# Memory.net
KiCad netlist of a schematic drawn in Altium Designer
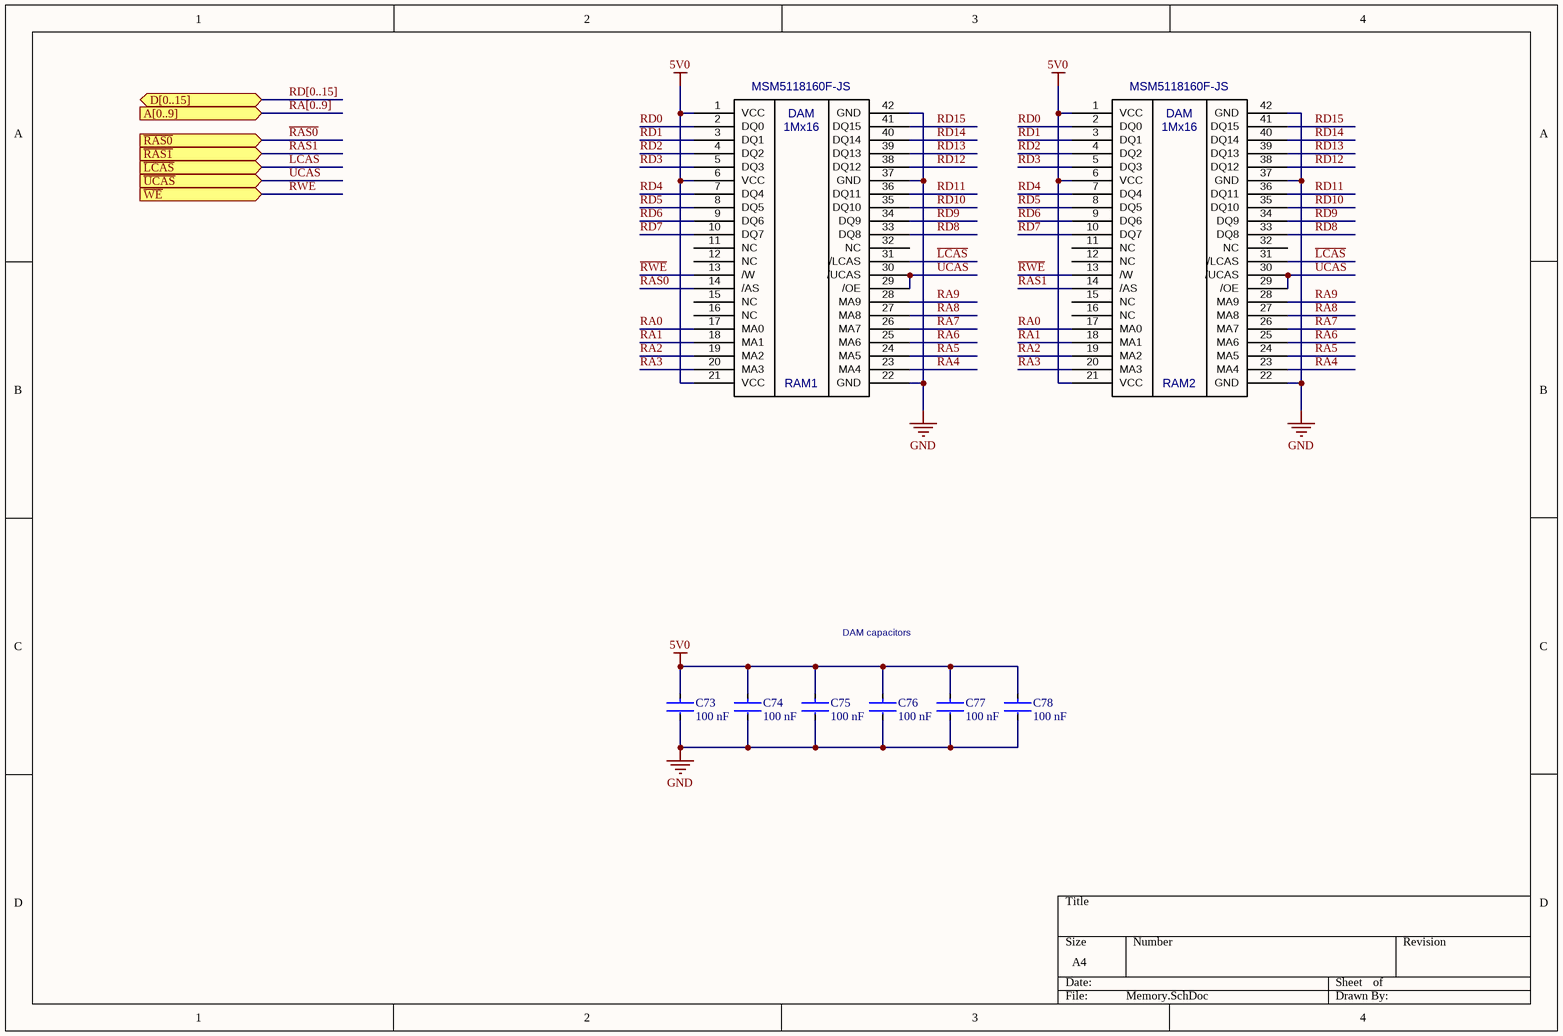
[diagram p0: Memory.SchDoc]

(export (version "E")
  (design (tool "Eeschema 10.0.6"))
  (components
    (comp (ref "C73")
      (value "CC0805-1.5pF")
      (footprint "CC0805")
      (description "CL21 Series 0805 1.5pF 50V ±0.25pF Tolerance C0G Multilayer Ceramic Chip Capacitor")
      (fields
        (field (name "MANUFACTURER PART NUMBER") "CL21C1R5CBANNNC")
        (field (name "CAPACITANCE") "100 nF")
        (field (name "MANUFACTURER") "Samsung")
      )
      (libsource (lib "zxevo") (part "CC0805"))
    )
    (comp (ref "C74")
      (value "CC0805-1.5pF")
      (footprint "CC0805")
      (description "CL21 Series 0805 1.5pF 50V ±0.25pF Tolerance C0G Multilayer Ceramic Chip Capacitor")
      (fields
        (field (name "MANUFACTURER PART NUMBER") "CL21C1R5CBANNNC")
        (field (name "CAPACITANCE") "100 nF")
        (field (name "MANUFACTURER") "Samsung")
      )
      (libsource (lib "zxevo") (part "CC0805"))
    )
    (comp (ref "C75")
      (value "CC0805-1.5pF")
      (footprint "CC0805")
      (description "CL21 Series 0805 1.5pF 50V ±0.25pF Tolerance C0G Multilayer Ceramic Chip Capacitor")
      (fields
        (field (name "MANUFACTURER PART NUMBER") "CL21C1R5CBANNNC")
        (field (name "CAPACITANCE") "100 nF")
        (field (name "MANUFACTURER") "Samsung")
      )
      (libsource (lib "zxevo") (part "CC0805"))
    )
    (comp (ref "C76")
      (value "CC0805-1.5pF")
      (footprint "CC0805")
      (description "CL21 Series 0805 1.5pF 50V ±0.25pF Tolerance C0G Multilayer Ceramic Chip Capacitor")
      (fields
        (field (name "MANUFACTURER PART NUMBER") "CL21C1R5CBANNNC")
        (field (name "CAPACITANCE") "100 nF")
        (field (name "MANUFACTURER") "Samsung")
      )
      (libsource (lib "zxevo") (part "CC0805"))
    )
    (comp (ref "C77")
      (value "CC0805-1.5pF")
      (footprint "CC0805")
      (description "CL21 Series 0805 1.5pF 50V ±0.25pF Tolerance C0G Multilayer Ceramic Chip Capacitor")
      (fields
        (field (name "MANUFACTURER PART NUMBER") "CL21C1R5CBANNNC")
        (field (name "CAPACITANCE") "100 nF")
        (field (name "MANUFACTURER") "Samsung")
      )
      (libsource (lib "zxevo") (part "CC0805"))
    )
    (comp (ref "C78")
      (value "CC0805-1.5pF")
      (footprint "CC0805")
      (description "CL21 Series 0805 1.5pF 50V ±0.25pF Tolerance C0G Multilayer Ceramic Chip Capacitor")
      (fields
        (field (name "MANUFACTURER PART NUMBER") "CL21C1R5CBANNNC")
        (field (name "CAPACITANCE") "100 nF")
        (field (name "MANUFACTURER") "Samsung")
      )
      (libsource (lib "zxevo") (part "CC0805"))
    )
    (comp (ref "RAM1")
      (value "MSM5118160F-JS")
      (footprint "SOJ42")
      (libsource (lib "zxevo") (part "MSM5118160F-JS"))
    )
    (comp (ref "RAM2")
      (value "MSM5118160F-JS")
      (footprint "SOJ42")
      (libsource (lib "zxevo") (part "MSM5118160F-JS"))
    )
  )
  (nets
    (net (code "1") (name "/RA0") (class "Default")
      (node (ref "RAM1") (pin "17") (pinfunction "MA0_17") (pintype "passive"))
      (node (ref "RAM2") (pin "17") (pinfunction "MA0_17") (pintype "passive"))
    )
    (net (code "2") (name "/RA1") (class "Default")
      (node (ref "RAM1") (pin "18") (pinfunction "MA1_18") (pintype "passive"))
      (node (ref "RAM2") (pin "18") (pinfunction "MA1_18") (pintype "passive"))
    )
    (net (code "3") (name "/RA2") (class "Default")
      (node (ref "RAM1") (pin "19") (pinfunction "MA2_19") (pintype "passive"))
      (node (ref "RAM2") (pin "19") (pinfunction "MA2_19") (pintype "passive"))
    )
    (net (code "4") (name "/RA3") (class "Default")
      (node (ref "RAM1") (pin "20") (pinfunction "MA3_20") (pintype "passive"))
      (node (ref "RAM2") (pin "20") (pinfunction "MA3_20") (pintype "passive"))
    )
    (net (code "5") (name "/RA4") (class "Default")
      (node (ref "RAM1") (pin "23") (pinfunction "MA4_23") (pintype "passive"))
      (node (ref "RAM2") (pin "23") (pinfunction "MA4_23") (pintype "passive"))
    )
    (net (code "6") (name "/RA5") (class "Default")
      (node (ref "RAM1") (pin "24") (pinfunction "MA5_24") (pintype "passive"))
      (node (ref "RAM2") (pin "24") (pinfunction "MA5_24") (pintype "passive"))
    )
    (net (code "7") (name "/RA6") (class "Default")
      (node (ref "RAM1") (pin "25") (pinfunction "MA6_25") (pintype "passive"))
      (node (ref "RAM2") (pin "25") (pinfunction "MA6_25") (pintype "passive"))
    )
    (net (code "8") (name "/RA7") (class "Default")
      (node (ref "RAM1") (pin "26") (pinfunction "MA7_26") (pintype "passive"))
      (node (ref "RAM2") (pin "26") (pinfunction "MA7_26") (pintype "passive"))
    )
    (net (code "9") (name "/RA8") (class "Default")
      (node (ref "RAM1") (pin "27") (pinfunction "MA8_27") (pintype "passive"))
      (node (ref "RAM2") (pin "27") (pinfunction "MA8_27") (pintype "passive"))
    )
    (net (code "10") (name "/RA9") (class "Default")
      (node (ref "RAM1") (pin "28") (pinfunction "MA9_28") (pintype "passive"))
      (node (ref "RAM2") (pin "28") (pinfunction "MA9_28") (pintype "passive"))
    )
    (net (code "12") (name "/RD0") (class "Default")
      (node (ref "RAM1") (pin "2") (pinfunction "DQ0_2") (pintype "passive"))
      (node (ref "RAM2") (pin "2") (pinfunction "DQ0_2") (pintype "passive"))
    )
    (net (code "13") (name "/RD1") (class "Default")
      (node (ref "RAM1") (pin "3") (pinfunction "DQ1_3") (pintype "passive"))
      (node (ref "RAM2") (pin "3") (pinfunction "DQ1_3") (pintype "passive"))
    )
    (net (code "14") (name "/RD2") (class "Default")
      (node (ref "RAM1") (pin "4") (pinfunction "DQ2_4") (pintype "passive"))
      (node (ref "RAM2") (pin "4") (pinfunction "DQ2_4") (pintype "passive"))
    )
    (net (code "15") (name "/RD3") (class "Default")
      (node (ref "RAM1") (pin "5") (pinfunction "DQ3_5") (pintype "passive"))
      (node (ref "RAM2") (pin "5") (pinfunction "DQ3_5") (pintype "passive"))
    )
    (net (code "16") (name "/RD4") (class "Default")
      (node (ref "RAM1") (pin "7") (pinfunction "DQ4_7") (pintype "passive"))
      (node (ref "RAM2") (pin "7") (pinfunction "DQ4_7") (pintype "passive"))
    )
    (net (code "17") (name "/RD5") (class "Default")
      (node (ref "RAM1") (pin "8") (pinfunction "DQ5_8") (pintype "passive"))
      (node (ref "RAM2") (pin "8") (pinfunction "DQ5_8") (pintype "passive"))
    )
    (net (code "18") (name "/RD6") (class "Default")
      (node (ref "RAM1") (pin "9") (pinfunction "DQ6_9") (pintype "passive"))
      (node (ref "RAM2") (pin "9") (pinfunction "DQ6_9") (pintype "passive"))
    )
    (net (code "19") (name "/RD7") (class "Default")
      (node (ref "RAM1") (pin "10") (pinfunction "DQ7_10") (pintype "passive"))
      (node (ref "RAM2") (pin "10") (pinfunction "DQ7_10") (pintype "passive"))
    )
    (net (code "20") (name "/RD8") (class "Default")
      (node (ref "RAM1") (pin "33") (pinfunction "DQ8_33") (pintype "passive"))
      (node (ref "RAM2") (pin "33") (pinfunction "DQ8_33") (pintype "passive"))
    )
    (net (code "21") (name "/RD9") (class "Default")
      (node (ref "RAM1") (pin "34") (pinfunction "DQ9_34") (pintype "passive"))
      (node (ref "RAM2") (pin "34") (pinfunction "DQ9_34") (pintype "passive"))
    )
    (net (code "22") (name "/RD10") (class "Default")
      (node (ref "RAM1") (pin "35") (pinfunction "DQ10_35") (pintype "passive"))
      (node (ref "RAM2") (pin "35") (pinfunction "DQ10_35") (pintype "passive"))
    )
    (net (code "23") (name "/RD11") (class "Default")
      (node (ref "RAM1") (pin "36") (pinfunction "DQ11_36") (pintype "passive"))
      (node (ref "RAM2") (pin "36") (pinfunction "DQ11_36") (pintype "passive"))
    )
    (net (code "24") (name "/RD12") (class "Default")
      (node (ref "RAM1") (pin "38") (pinfunction "DQ12_38") (pintype "passive"))
      (node (ref "RAM2") (pin "38") (pinfunction "DQ12_38") (pintype "passive"))
    )
    (net (code "25") (name "/RD13") (class "Default")
      (node (ref "RAM1") (pin "39") (pinfunction "DQ13_39") (pintype "passive"))
      (node (ref "RAM2") (pin "39") (pinfunction "DQ13_39") (pintype "passive"))
    )
    (net (code "26") (name "/RD14") (class "Default")
      (node (ref "RAM1") (pin "40") (pinfunction "DQ14_40") (pintype "passive"))
      (node (ref "RAM2") (pin "40") (pinfunction "DQ14_40") (pintype "passive"))
    )
    (net (code "27") (name "/RD15") (class "Default")
      (node (ref "RAM1") (pin "41") (pinfunction "DQ15_41") (pintype "passive"))
      (node (ref "RAM2") (pin "41") (pinfunction "DQ15_41") (pintype "passive"))
    )
    (net (code "29") (name "/~{LCAS}") (class "Default")
      (node (ref "RAM1") (pin "31") (pinfunction "/LCAS_31") (pintype "passive"))
      (node (ref "RAM2") (pin "31") (pinfunction "/LCAS_31") (pintype "passive"))
    )
    (net (code "30") (name "/~{RAS0}") (class "Default")
      (node (ref "RAM1") (pin "14") (pinfunction "/AS_14") (pintype "passive"))
    )
    (net (code "31") (name "/~{RAS1}") (class "Default")
      (node (ref "RAM2") (pin "14") (pinfunction "/AS_14") (pintype "passive"))
    )
    (net (code "32") (name "/~{RWE}") (class "Default")
      (node (ref "RAM1") (pin "13") (pinfunction "/W_13") (pintype "passive"))
      (node (ref "RAM2") (pin "13") (pinfunction "/W_13") (pintype "passive"))
    )
    (net (code "33") (name "/~{UCAS}") (class "Default")
      (node (ref "RAM1") (pin "29") (pinfunction "/OE_29") (pintype "passive"))
      (node (ref "RAM1") (pin "30") (pinfunction "/UCAS_30") (pintype "passive"))
      (node (ref "RAM2") (pin "29") (pinfunction "/OE_29") (pintype "passive"))
      (node (ref "RAM2") (pin "30") (pinfunction "/UCAS_30") (pintype "passive"))
    )
    (net (code "34") (name "5V0") (class "Default")
      (node (ref "C73") (pin "1") (pinfunction "1_1") (pintype "passive"))
      (node (ref "C74") (pin "1") (pinfunction "1_1") (pintype "passive"))
      (node (ref "C75") (pin "1") (pinfunction "1_1") (pintype "passive"))
      (node (ref "C76") (pin "1") (pinfunction "1_1") (pintype "passive"))
      (node (ref "C77") (pin "1") (pinfunction "1_1") (pintype "passive"))
      (node (ref "C78") (pin "1") (pinfunction "1_1") (pintype "passive"))
      (node (ref "RAM1") (pin "1") (pinfunction "VCC_1") (pintype "passive"))
      (node (ref "RAM1") (pin "21") (pinfunction "VCC_21") (pintype "passive"))
      (node (ref "RAM1") (pin "6") (pinfunction "VCC_6") (pintype "passive"))
      (node (ref "RAM2") (pin "1") (pinfunction "VCC_1") (pintype "passive"))
      (node (ref "RAM2") (pin "21") (pinfunction "VCC_21") (pintype "passive"))
      (node (ref "RAM2") (pin "6") (pinfunction "VCC_6") (pintype "passive"))
    )
    (net (code "35") (name "GND") (class "Default")
      (node (ref "C73") (pin "2") (pinfunction "2_2") (pintype "passive"))
      (node (ref "C74") (pin "2") (pinfunction "2_2") (pintype "passive"))
      (node (ref "C75") (pin "2") (pinfunction "2_2") (pintype "passive"))
      (node (ref "C76") (pin "2") (pinfunction "2_2") (pintype "passive"))
      (node (ref "C77") (pin "2") (pinfunction "2_2") (pintype "passive"))
      (node (ref "C78") (pin "2") (pinfunction "2_2") (pintype "passive"))
      (node (ref "RAM1") (pin "22") (pinfunction "GND_22") (pintype "passive"))
      (node (ref "RAM1") (pin "37") (pinfunction "GND_37") (pintype "passive"))
      (node (ref "RAM1") (pin "42") (pinfunction "GND_42") (pintype "passive"))
      (node (ref "RAM2") (pin "22") (pinfunction "GND_22") (pintype "passive"))
      (node (ref "RAM2") (pin "37") (pinfunction "GND_37") (pintype "passive"))
      (node (ref "RAM2") (pin "42") (pinfunction "GND_42") (pintype "passive"))
    )
    (net (code "36") (name "unconnected-(RAM1-NC-Pad11)") (class "Default")
      (node (ref "RAM1") (pin "11") (pinfunction "NC_11") (pintype "passive"))
    )
    (net (code "37") (name "unconnected-(RAM1-NC-Pad12)") (class "Default")
      (node (ref "RAM1") (pin "12") (pinfunction "NC_12") (pintype "passive"))
    )
    (net (code "38") (name "unconnected-(RAM1-NC-Pad15)") (class "Default")
      (node (ref "RAM1") (pin "15") (pinfunction "NC_15") (pintype "passive"))
    )
    (net (code "39") (name "unconnected-(RAM1-NC-Pad16)") (class "Default")
      (node (ref "RAM1") (pin "16") (pinfunction "NC_16") (pintype "passive"))
    )
    (net (code "40") (name "unconnected-(RAM1-NC-Pad32)") (class "Default")
      (node (ref "RAM1") (pin "32") (pinfunction "NC_32") (pintype "passive"))
    )
    (net (code "41") (name "unconnected-(RAM2-NC-Pad11)") (class "Default")
      (node (ref "RAM2") (pin "11") (pinfunction "NC_11") (pintype "passive"))
    )
    (net (code "42") (name "unconnected-(RAM2-NC-Pad12)") (class "Default")
      (node (ref "RAM2") (pin "12") (pinfunction "NC_12") (pintype "passive"))
    )
    (net (code "43") (name "unconnected-(RAM2-NC-Pad15)") (class "Default")
      (node (ref "RAM2") (pin "15") (pinfunction "NC_15") (pintype "passive"))
    )
    (net (code "44") (name "unconnected-(RAM2-NC-Pad16)") (class "Default")
      (node (ref "RAM2") (pin "16") (pinfunction "NC_16") (pintype "passive"))
    )
    (net (code "45") (name "unconnected-(RAM2-NC-Pad32)") (class "Default")
      (node (ref "RAM2") (pin "32") (pinfunction "NC_32") (pintype "passive"))
    )
  )
)
